# airwisk.net
KiCad netlist of a schematic drawn in EAGLE
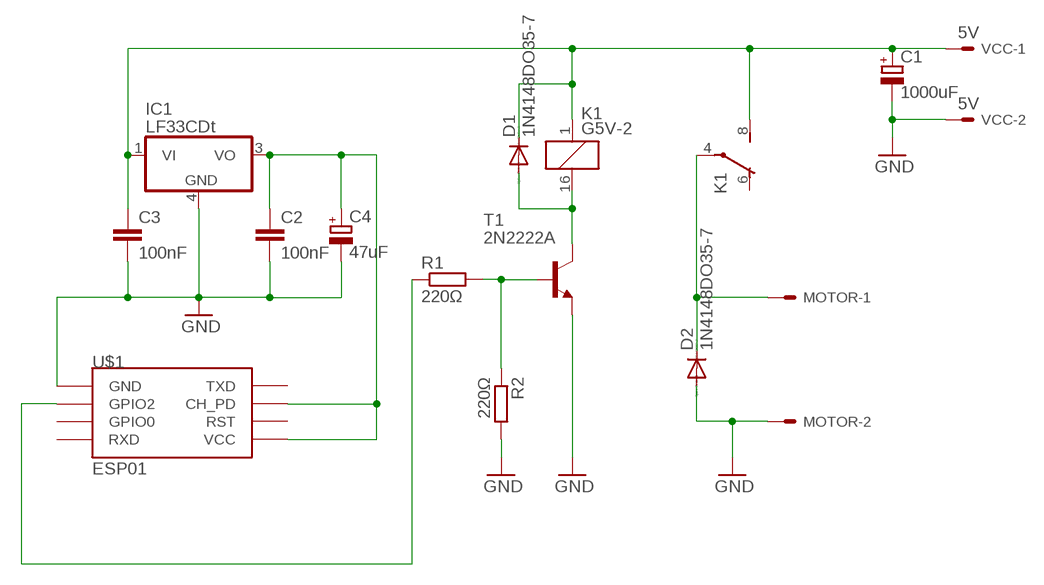
[diagram p0: schematic, sheet 1]

(export (version "E")
  (design (tool "Eeschema 10.0.6"))
  (components
    (comp (ref "C1")
      (value "1000uF")
      (footprint "eagle-import:E3,5-8")
      (libsource (lib "eagle-import") (part "CPOL-EUE3.5-8"))
    )
    (comp (ref "C2")
      (value "100nF")
      (footprint "eagle-import:C025-025X050")
      (libsource (lib "eagle-import") (part "C-EU025-025X050"))
    )
    (comp (ref "C3")
      (value "100nF")
      (footprint "eagle-import:C025-025X050")
      (libsource (lib "eagle-import") (part "C-EU025-025X050"))
    )
    (comp (ref "C4")
      (value "47uF")
      (footprint "eagle-import:E2-5")
      (libsource (lib "eagle-import") (part "CPOL-EUE2-5"))
    )
    (comp (ref "D1")
      (value "1N4148DO35-7")
      (footprint "eagle-import:DO35-7")
      (libsource (lib "eagle-import") (part "1N4148DO35-7"))
    )
    (comp (ref "D2")
      (value "1N4148DO35-7")
      (footprint "eagle-import:DO35-7")
      (libsource (lib "eagle-import") (part "1N4148DO35-7"))
    )
    (comp (ref "IC1")
      (value "LF33CDt")
      (footprint "eagle-import:DPACK_3")
      (libsource (lib "eagle-import") (part "MC78M05ABDT"))
    )
    (comp (ref "K1")
      (value "G5V-2")
      (footprint "eagle-import:G5V-2")
      (fields (field (name "MPN") "G5V-2 5DC"))
      (libsource (lib "eagle-import") (part "G5V-2"))
    )
    (comp (ref "MOTOR")
      (value "332-02")
      (footprint "eagle-import:332-02")
      (libsource (lib "eagle-import") (part "332-02"))
    )
    (comp (ref "R1")
      (value "220Ω")
      (footprint "eagle-import:0204_7")
      (libsource (lib "eagle-import") (part "R-EU_0204/7"))
    )
    (comp (ref "R2")
      (value "220Ω")
      (footprint "eagle-import:0204_7")
      (libsource (lib "eagle-import") (part "R-EU_0204/7"))
    )
    (comp (ref "T1")
      (value "2N2222A")
      (footprint "eagle-import:TO92")
      (libsource (lib "eagle-import") (part "-NPN-TO92"))
    )
    (comp (ref "U$1")
      (value "ESP01")
      (footprint "eagle-import:ESP01")
      (libsource (lib "eagle-import") (part "ESP01"))
    )
    (comp (ref "VCC")
      (value "5V")
      (footprint "eagle-import:332-02")
      (libsource (lib "eagle-import") (part "332-02"))
    )
  )
  (nets
    (net (code "1") (name "GND") (class "Default")
      (node (ref "C1") (pin "-") (pinfunction "-_-") (pintype "passive"))
      (node (ref "C2") (pin "2") (pinfunction "2_2") (pintype "passive"))
      (node (ref "C3") (pin "2") (pinfunction "2_2") (pintype "passive"))
      (node (ref "C4") (pin "-") (pinfunction "-_-") (pintype "passive"))
      (node (ref "D2") (pin "A") (pinfunction "A_A") (pintype "passive"))
      (node (ref "IC1") (pin "4") (pinfunction "GND_4") (pintype "passive"))
      (node (ref "MOTOR") (pin "2") (pinfunction "S_2") (pintype "passive"))
      (node (ref "R2") (pin "2") (pinfunction "2_2") (pintype "passive"))
      (node (ref "T1") (pin "1") (pinfunction "E_1") (pintype "passive"))
      (node (ref "U$1") (pin "GND") (pinfunction "GND_GND") (pintype "bidirectional"))
      (node (ref "VCC") (pin "2") (pinfunction "S_2") (pintype "passive"))
    )
    (net (code "2") (name "Net-(IC1-VI)") (class "Default")
      (node (ref "C1") (pin "+") (pinfunction "+_+") (pintype "passive"))
      (node (ref "C3") (pin "1") (pinfunction "1_1") (pintype "passive"))
      (node (ref "D1") (pin "C") (pinfunction "C_C") (pintype "passive"))
      (node (ref "IC1") (pin "1") (pinfunction "VI_1") (pintype "input"))
      (node (ref "K1") (pin "1") (pinfunction "1_1") (pintype "passive"))
      (node (ref "K1") (pin "8") (pinfunction "S_8") (pintype "passive"))
      (node (ref "VCC") (pin "1") (pinfunction "S_1") (pintype "passive"))
    )
    (net (code "3") (name "Net-(IC1-VO)") (class "Default")
      (node (ref "C2") (pin "1") (pinfunction "1_1") (pintype "passive"))
      (node (ref "C4") (pin "+") (pinfunction "+_+") (pintype "passive"))
      (node (ref "IC1") (pin "3") (pinfunction "VO_3") (pintype "passive"))
      (node (ref "U$1") (pin "CH_PD") (pinfunction "CH_PD_CH_PD") (pintype "bidirectional"))
      (node (ref "U$1") (pin "VCC") (pinfunction "VCC_VCC") (pintype "bidirectional"))
    )
    (net (code "4") (name "Net-(K1A-P)") (class "Default")
      (node (ref "D2") (pin "C") (pinfunction "C_C") (pintype "passive"))
      (node (ref "K1") (pin "4") (pinfunction "P_4") (pintype "passive"))
      (node (ref "MOTOR") (pin "1") (pinfunction "S_1") (pintype "passive"))
    )
    (net (code "5") (name "Net-(K1C-2)") (class "Default")
      (node (ref "D1") (pin "A") (pinfunction "A_A") (pintype "passive"))
      (node (ref "K1") (pin "16") (pinfunction "2_16") (pintype "passive"))
      (node (ref "T1") (pin "3") (pinfunction "C_3") (pintype "passive"))
    )
    (net (code "6") (name "Net-(R1-Pad1)") (class "Default")
      (node (ref "R1") (pin "1") (pinfunction "1_1") (pintype "passive"))
      (node (ref "U$1") (pin "GPIO2") (pinfunction "GPIO2_GPIO2") (pintype "bidirectional"))
    )
    (net (code "7") (name "Net-(T1-B)") (class "Default")
      (node (ref "R1") (pin "2") (pinfunction "2_2") (pintype "passive"))
      (node (ref "R2") (pin "1") (pinfunction "1_1") (pintype "passive"))
      (node (ref "T1") (pin "2") (pinfunction "B_2") (pintype "passive"))
    )
    (net (code "8") (name "unconnected-(K1A-O-Pad6)") (class "Default")
      (node (ref "K1") (pin "6") (pinfunction "O_6") (pintype "passive"))
    )
    (net (code "9") (name "unconnected-(U$1-PadGPIO0)") (class "Default")
      (node (ref "U$1") (pin "GPIO0") (pinfunction "GPIO0_GPIO0") (pintype "bidirectional"))
    )
    (net (code "10") (name "unconnected-(U$1-PadRST)") (class "Default")
      (node (ref "U$1") (pin "RST") (pinfunction "RST_RST") (pintype "bidirectional"))
    )
    (net (code "11") (name "unconnected-(U$1-RXD-PadRX)") (class "Default")
      (node (ref "U$1") (pin "RX") (pinfunction "RXD_RX") (pintype "bidirectional"))
    )
    (net (code "12") (name "unconnected-(U$1-TXD-PadTX)") (class "Default")
      (node (ref "U$1") (pin "TX") (pinfunction "TXD_TX") (pintype "bidirectional"))
    )
  )
)
